# CAM_SENSOR.net
KiCad netlist of a schematic drawn in Altium Designer
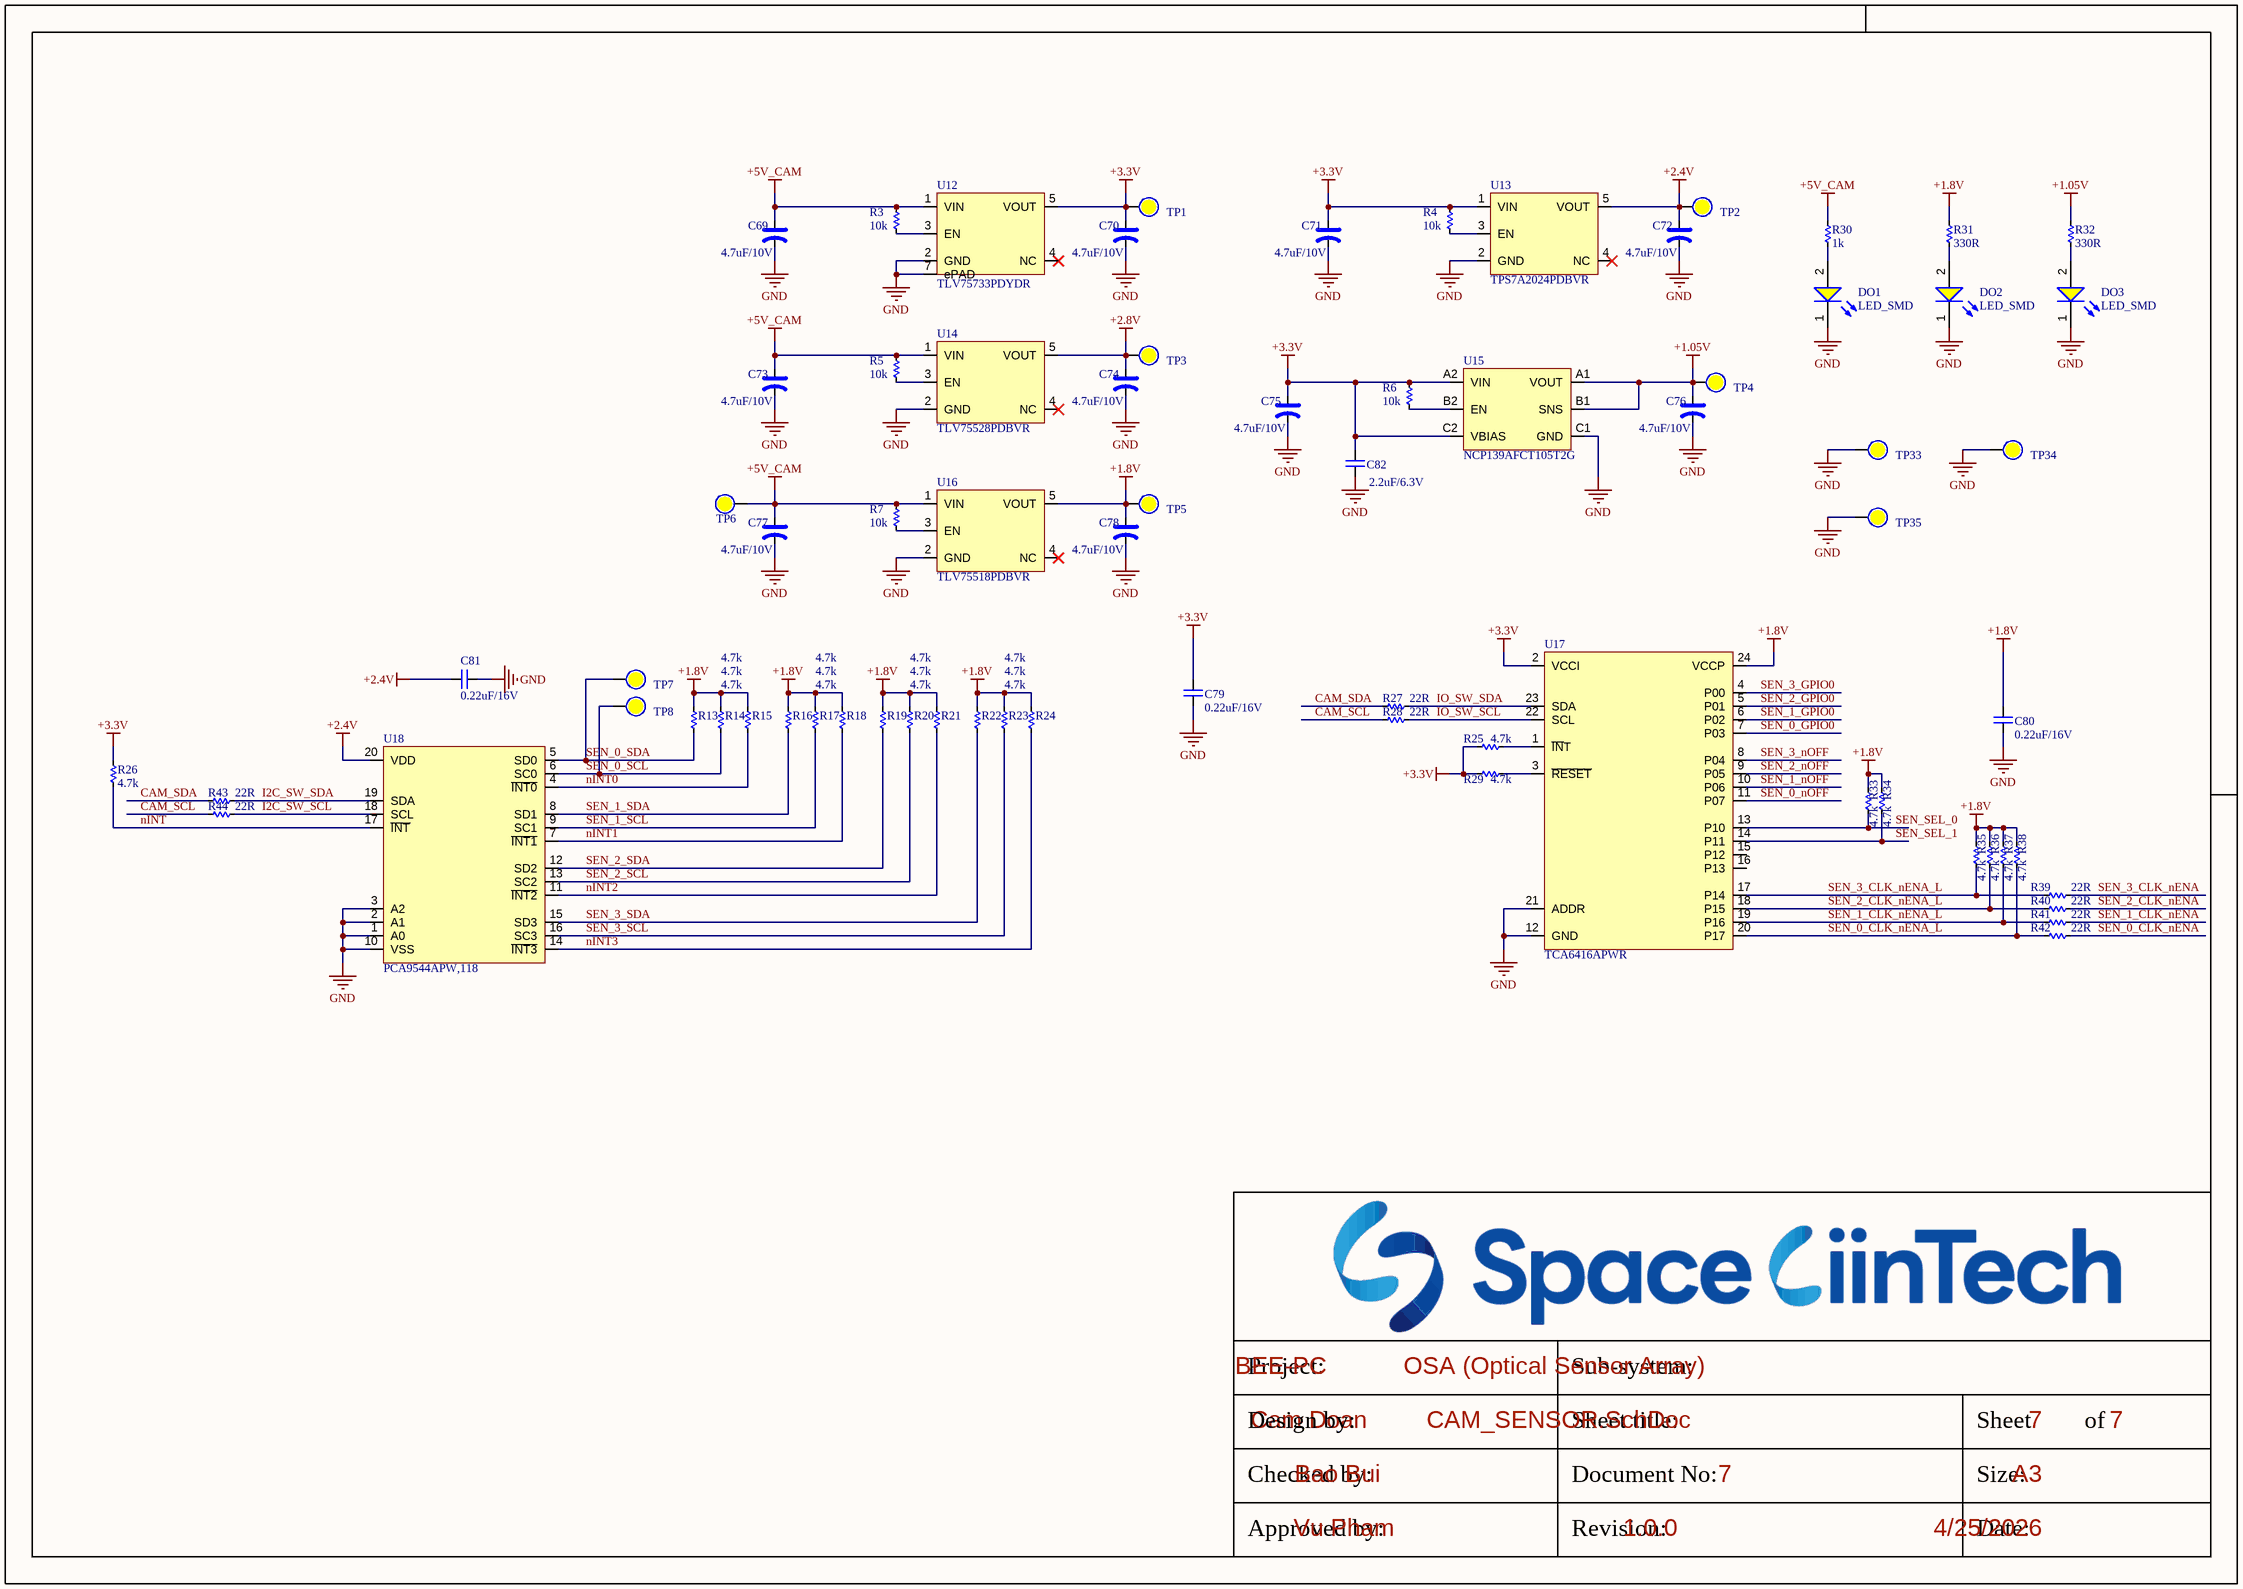
[diagram p0: CAM_SENSOR.SchDoc]

(export (version "E")
  (design (tool "Eeschema 10.0.6"))
  (components
    (comp (ref "C69")
      (value "4.7uF/10V")
      (footprint "CAP_MP_1608X90")
      (description "CAP_Polarization")
      (fields (field (name "PUBLISHER") "Altium Limited"))
      (libsource (lib "LABLIB") (part "CAP_TH"))
    )
    (comp (ref "C70")
      (value "4.7uF/10V")
      (footprint "CAP_MP_1608X90")
      (description "CAP_Polarization")
      (fields (field (name "PUBLISHER") "Altium Limited"))
      (libsource (lib "LABLIB") (part "CAP_TH"))
    )
    (comp (ref "C71")
      (value "4.7uF/10V")
      (footprint "CAP_MP_1608X90")
      (description "CAP_Polarization")
      (fields (field (name "PUBLISHER") "Altium Limited"))
      (libsource (lib "LABLIB") (part "CAP_TH"))
    )
    (comp (ref "C72")
      (value "4.7uF/10V")
      (footprint "CAP_MP_1608X90")
      (description "CAP_Polarization")
      (fields (field (name "PUBLISHER") "Altium Limited"))
      (libsource (lib "LABLIB") (part "CAP_TH"))
    )
    (comp (ref "C73")
      (value "4.7uF/10V")
      (footprint "CAP_MP_1608X90")
      (description "CAP_Polarization")
      (fields (field (name "PUBLISHER") "Altium Limited"))
      (libsource (lib "LABLIB") (part "CAP_TH"))
    )
    (comp (ref "C74")
      (value "4.7uF/10V")
      (footprint "CAP_MP_1608X90")
      (description "CAP_Polarization")
      (fields (field (name "PUBLISHER") "Altium Limited"))
      (libsource (lib "LABLIB") (part "CAP_TH"))
    )
    (comp (ref "C75")
      (value "4.7uF/10V")
      (footprint "CAP_MP_1608X90")
      (description "CAP_Polarization")
      (fields (field (name "PUBLISHER") "Altium Limited"))
      (libsource (lib "LABLIB") (part "CAP_TH"))
    )
    (comp (ref "C76")
      (value "4.7uF/10V")
      (footprint "CAP_MP_1608X90")
      (description "CAP_Polarization")
      (fields (field (name "PUBLISHER") "Altium Limited"))
      (libsource (lib "LABLIB") (part "CAP_TH"))
    )
    (comp (ref "C77")
      (value "4.7uF/10V")
      (footprint "CAP_MP_1608X90")
      (description "CAP_Polarization")
      (fields (field (name "PUBLISHER") "Altium Limited"))
      (libsource (lib "LABLIB") (part "CAP_TH"))
    )
    (comp (ref "C78")
      (value "4.7uF/10V")
      (footprint "CAP_MP_1608X90")
      (description "CAP_Polarization")
      (fields (field (name "PUBLISHER") "Altium Limited"))
      (libsource (lib "LABLIB") (part "CAP_TH"))
    )
    (comp (ref "C79")
      (value "0.22uF/16V")
      (footprint "CAP_C_1005X60")
      (description "CAP_Chip")
      (libsource (lib "LABLIB") (part "CAP_SMD"))
    )
    (comp (ref "C80")
      (value "0.22uF/16V")
      (footprint "CAP_C_1005X60")
      (description "CAP_Chip")
      (libsource (lib "LABLIB") (part "CAP_SMD"))
    )
    (comp (ref "C81")
      (value "0.22uF/16V")
      (footprint "CAP_C_1005X60")
      (description "CAP_Chip")
      (libsource (lib "LABLIB") (part "CAP_SMD"))
    )
    (comp (ref "C82")
      (value "2.2uF/6.3V")
      (footprint "CAP_C_1005X60")
      (description "CAP_Chip")
      (libsource (lib "LABLIB") (part "CAP_SMD"))
    )
    (comp (ref "DO1") (value "LED_SMD") (footprint "LED_0603") (libsource (lib "LABLIB") (part "LED_SMD")))
    (comp (ref "DO2") (value "LED_SMD") (footprint "LED_0603") (libsource (lib "LABLIB") (part "LED_SMD")))
    (comp (ref "DO3") (value "LED_SMD") (footprint "LED_0603") (libsource (lib "LABLIB") (part "LED_SMD")))
    (comp (ref "R3")
      (value "10k")
      (footprint "RES_C_1005X40")
      (description "RES-Chip")
      (fields
        (field (name "MANUFACTURER") "Generic Components")
        (field (name "PUBLISHER") "Altium Hobart Technology Centre")
      )
      (libsource (lib "LABLIB") (part "RES-SMD"))
    )
    (comp (ref "R4")
      (value "10k")
      (footprint "RES_C_1005X40")
      (description "RES-Chip")
      (fields
        (field (name "MANUFACTURER") "Generic Components")
        (field (name "PUBLISHER") "Altium Hobart Technology Centre")
      )
      (libsource (lib "LABLIB") (part "RES-SMD"))
    )
    (comp (ref "R5")
      (value "10k")
      (footprint "RES_C_1005X40")
      (description "RES-Chip")
      (fields
        (field (name "MANUFACTURER") "Generic Components")
        (field (name "PUBLISHER") "Altium Hobart Technology Centre")
      )
      (libsource (lib "LABLIB") (part "RES-SMD"))
    )
    (comp (ref "R6")
      (value "10k")
      (footprint "RES_C_1005X40")
      (description "RES-Chip")
      (fields
        (field (name "MANUFACTURER") "Generic Components")
        (field (name "PUBLISHER") "Altium Hobart Technology Centre")
      )
      (libsource (lib "LABLIB") (part "RES-SMD"))
    )
    (comp (ref "R7")
      (value "10k")
      (footprint "RES_C_1005X40")
      (description "RES-Chip")
      (fields
        (field (name "MANUFACTURER") "Generic Components")
        (field (name "PUBLISHER") "Altium Hobart Technology Centre")
      )
      (libsource (lib "LABLIB") (part "RES-SMD"))
    )
    (comp (ref "R13")
      (value "4.7k")
      (footprint "RES_C_1005X40")
      (description "RES-Chip")
      (fields
        (field (name "MANUFACTURER") "Generic Components")
        (field (name "PUBLISHER") "Altium Hobart Technology Centre")
      )
      (libsource (lib "LABLIB") (part "RES-SMD"))
    )
    (comp (ref "R14")
      (value "4.7k")
      (footprint "RES_C_1005X40")
      (description "RES-Chip")
      (fields
        (field (name "MANUFACTURER") "Generic Components")
        (field (name "PUBLISHER") "Altium Hobart Technology Centre")
      )
      (libsource (lib "LABLIB") (part "RES-SMD"))
    )
    (comp (ref "R15")
      (value "4.7k")
      (footprint "RES_C_1005X40")
      (description "RES-Chip")
      (fields
        (field (name "MANUFACTURER") "Generic Components")
        (field (name "PUBLISHER") "Altium Hobart Technology Centre")
      )
      (libsource (lib "LABLIB") (part "RES-SMD"))
    )
    (comp (ref "R16")
      (value "4.7k")
      (footprint "RES_C_1005X40")
      (description "RES-Chip")
      (fields
        (field (name "MANUFACTURER") "Generic Components")
        (field (name "PUBLISHER") "Altium Hobart Technology Centre")
      )
      (libsource (lib "LABLIB") (part "RES-SMD"))
    )
    (comp (ref "R17")
      (value "4.7k")
      (footprint "RES_C_1005X40")
      (description "RES-Chip")
      (fields
        (field (name "MANUFACTURER") "Generic Components")
        (field (name "PUBLISHER") "Altium Hobart Technology Centre")
      )
      (libsource (lib "LABLIB") (part "RES-SMD"))
    )
    (comp (ref "R18")
      (value "4.7k")
      (footprint "RES_C_1005X40")
      (description "RES-Chip")
      (fields
        (field (name "MANUFACTURER") "Generic Components")
        (field (name "PUBLISHER") "Altium Hobart Technology Centre")
      )
      (libsource (lib "LABLIB") (part "RES-SMD"))
    )
    (comp (ref "R19")
      (value "4.7k")
      (footprint "RES_C_1005X40")
      (description "RES-Chip")
      (fields
        (field (name "MANUFACTURER") "Generic Components")
        (field (name "PUBLISHER") "Altium Hobart Technology Centre")
      )
      (libsource (lib "LABLIB") (part "RES-SMD"))
    )
    (comp (ref "R20")
      (value "4.7k")
      (footprint "RES_C_1005X40")
      (description "RES-Chip")
      (fields
        (field (name "MANUFACTURER") "Generic Components")
        (field (name "PUBLISHER") "Altium Hobart Technology Centre")
      )
      (libsource (lib "LABLIB") (part "RES-SMD"))
    )
    (comp (ref "R21")
      (value "4.7k")
      (footprint "RES_C_1005X40")
      (description "RES-Chip")
      (fields
        (field (name "MANUFACTURER") "Generic Components")
        (field (name "PUBLISHER") "Altium Hobart Technology Centre")
      )
      (libsource (lib "LABLIB") (part "RES-SMD"))
    )
    (comp (ref "R22")
      (value "4.7k")
      (footprint "RES_C_1005X40")
      (description "RES-Chip")
      (fields
        (field (name "MANUFACTURER") "Generic Components")
        (field (name "PUBLISHER") "Altium Hobart Technology Centre")
      )
      (libsource (lib "LABLIB") (part "RES-SMD"))
    )
    (comp (ref "R23")
      (value "4.7k")
      (footprint "RES_C_1005X40")
      (description "RES-Chip")
      (fields
        (field (name "MANUFACTURER") "Generic Components")
        (field (name "PUBLISHER") "Altium Hobart Technology Centre")
      )
      (libsource (lib "LABLIB") (part "RES-SMD"))
    )
    (comp (ref "R24")
      (value "4.7k")
      (footprint "RES_C_1005X40")
      (description "RES-Chip")
      (fields
        (field (name "MANUFACTURER") "Generic Components")
        (field (name "PUBLISHER") "Altium Hobart Technology Centre")
      )
      (libsource (lib "LABLIB") (part "RES-SMD"))
    )
    (comp (ref "R25")
      (value "4.7k")
      (footprint "RES_C_1005X40")
      (description "RES-Chip")
      (fields
        (field (name "MANUFACTURER") "Generic Components")
        (field (name "PUBLISHER") "Altium Hobart Technology Centre")
      )
      (libsource (lib "LABLIB") (part "RES-SMD"))
    )
    (comp (ref "R26")
      (value "4.7k")
      (footprint "RES_C_1005X40")
      (description "RES-Chip")
      (fields
        (field (name "MANUFACTURER") "Generic Components")
        (field (name "PUBLISHER") "Altium Hobart Technology Centre")
      )
      (libsource (lib "LABLIB") (part "RES-SMD"))
    )
    (comp (ref "R27")
      (value "22R")
      (footprint "RES_C_1005X40")
      (description "RES-Chip")
      (fields
        (field (name "MANUFACTURER") "Generic Components")
        (field (name "PUBLISHER") "Altium Hobart Technology Centre")
      )
      (libsource (lib "LABLIB") (part "RES-SMD"))
    )
    (comp (ref "R28")
      (value "22R")
      (footprint "RES_C_1005X40")
      (description "RES-Chip")
      (fields
        (field (name "MANUFACTURER") "Generic Components")
        (field (name "PUBLISHER") "Altium Hobart Technology Centre")
      )
      (libsource (lib "LABLIB") (part "RES-SMD"))
    )
    (comp (ref "R29")
      (value "4.7k")
      (footprint "RES_C_1005X40")
      (description "RES-Chip")
      (fields
        (field (name "MANUFACTURER") "Generic Components")
        (field (name "PUBLISHER") "Altium Hobart Technology Centre")
      )
      (libsource (lib "LABLIB") (part "RES-SMD"))
    )
    (comp (ref "R30")
      (value "1k")
      (footprint "RES_C_1005X40")
      (description "RES-Chip")
      (fields
        (field (name "MANUFACTURER") "Generic Components")
        (field (name "PUBLISHER") "Altium Hobart Technology Centre")
      )
      (libsource (lib "LABLIB") (part "RES-SMD"))
    )
    (comp (ref "R31")
      (value "330R")
      (footprint "RES_C_1005X40")
      (description "RES-Chip")
      (fields
        (field (name "MANUFACTURER") "Generic Components")
        (field (name "PUBLISHER") "Altium Hobart Technology Centre")
      )
      (libsource (lib "LABLIB") (part "RES-SMD"))
    )
    (comp (ref "R32")
      (value "330R")
      (footprint "RES_C_1005X40")
      (description "RES-Chip")
      (fields
        (field (name "MANUFACTURER") "Generic Components")
        (field (name "PUBLISHER") "Altium Hobart Technology Centre")
      )
      (libsource (lib "LABLIB") (part "RES-SMD"))
    )
    (comp (ref "R33")
      (value "4.7k")
      (footprint "RES_C_1005X40")
      (description "RES-Chip")
      (fields
        (field (name "MANUFACTURER") "Generic Components")
        (field (name "PUBLISHER") "Altium Hobart Technology Centre")
      )
      (libsource (lib "LABLIB") (part "RES-SMD"))
    )
    (comp (ref "R34")
      (value "4.7k")
      (footprint "RES_C_1005X40")
      (description "RES-Chip")
      (fields
        (field (name "MANUFACTURER") "Generic Components")
        (field (name "PUBLISHER") "Altium Hobart Technology Centre")
      )
      (libsource (lib "LABLIB") (part "RES-SMD"))
    )
    (comp (ref "R35")
      (value "4.7k")
      (footprint "RES_C_1005X40")
      (description "RES-Chip")
      (fields
        (field (name "MANUFACTURER") "Generic Components")
        (field (name "PUBLISHER") "Altium Hobart Technology Centre")
      )
      (libsource (lib "LABLIB") (part "RES-SMD"))
    )
    (comp (ref "R36")
      (value "4.7k")
      (footprint "RES_C_1005X40")
      (description "RES-Chip")
      (fields
        (field (name "MANUFACTURER") "Generic Components")
        (field (name "PUBLISHER") "Altium Hobart Technology Centre")
      )
      (libsource (lib "LABLIB") (part "RES-SMD"))
    )
    (comp (ref "R37")
      (value "4.7k")
      (footprint "RES_C_1005X40")
      (description "RES-Chip")
      (fields
        (field (name "MANUFACTURER") "Generic Components")
        (field (name "PUBLISHER") "Altium Hobart Technology Centre")
      )
      (libsource (lib "LABLIB") (part "RES-SMD"))
    )
    (comp (ref "R38")
      (value "4.7k")
      (footprint "RES_C_1005X40")
      (description "RES-Chip")
      (fields
        (field (name "MANUFACTURER") "Generic Components")
        (field (name "PUBLISHER") "Altium Hobart Technology Centre")
      )
      (libsource (lib "LABLIB") (part "RES-SMD"))
    )
    (comp (ref "R39")
      (value "22R")
      (footprint "RES_C_1005X40")
      (description "RES-Chip")
      (fields
        (field (name "MANUFACTURER") "Generic Components")
        (field (name "PUBLISHER") "Altium Hobart Technology Centre")
      )
      (libsource (lib "LABLIB") (part "RES-SMD"))
    )
    (comp (ref "R40")
      (value "22R")
      (footprint "RES_C_1005X40")
      (description "RES-Chip")
      (fields
        (field (name "MANUFACTURER") "Generic Components")
        (field (name "PUBLISHER") "Altium Hobart Technology Centre")
      )
      (libsource (lib "LABLIB") (part "RES-SMD"))
    )
    (comp (ref "R41")
      (value "22R")
      (footprint "RES_C_1005X40")
      (description "RES-Chip")
      (fields
        (field (name "MANUFACTURER") "Generic Components")
        (field (name "PUBLISHER") "Altium Hobart Technology Centre")
      )
      (libsource (lib "LABLIB") (part "RES-SMD"))
    )
    (comp (ref "R42")
      (value "22R")
      (footprint "RES_C_1005X40")
      (description "RES-Chip")
      (fields
        (field (name "MANUFACTURER") "Generic Components")
        (field (name "PUBLISHER") "Altium Hobart Technology Centre")
      )
      (libsource (lib "LABLIB") (part "RES-SMD"))
    )
    (comp (ref "R43")
      (value "22R")
      (footprint "RES_C_1005X40")
      (description "RES-Chip")
      (fields
        (field (name "MANUFACTURER") "Generic Components")
        (field (name "PUBLISHER") "Altium Hobart Technology Centre")
      )
      (libsource (lib "LABLIB") (part "RES-SMD"))
    )
    (comp (ref "R44")
      (value "22R")
      (footprint "RES_C_1005X40")
      (description "RES-Chip")
      (fields
        (field (name "MANUFACTURER") "Generic Components")
        (field (name "PUBLISHER") "Altium Hobart Technology Centre")
      )
      (libsource (lib "LABLIB") (part "RES-SMD"))
    )
    (comp (ref "TP1")
      (value "~")
      (footprint "Testpoint_80_pin0")
      (description "Test Point")
      (libsource (lib "LABLIB") (part "Test Point"))
    )
    (comp (ref "TP2")
      (value "~")
      (footprint "Testpoint_80_pin0")
      (description "Test Point")
      (libsource (lib "LABLIB") (part "Test Point"))
    )
    (comp (ref "TP3")
      (value "~")
      (footprint "Testpoint_80_pin0")
      (description "Test Point")
      (libsource (lib "LABLIB") (part "Test Point"))
    )
    (comp (ref "TP4")
      (value "~")
      (footprint "Testpoint_80_pin0")
      (description "Test Point")
      (libsource (lib "LABLIB") (part "Test Point"))
    )
    (comp (ref "TP5")
      (value "~")
      (footprint "Testpoint_80_pin0")
      (description "Test Point")
      (libsource (lib "LABLIB") (part "Test Point"))
    )
    (comp (ref "TP6")
      (value "~")
      (footprint "Testpoint_80_pin0")
      (description "Test Point")
      (libsource (lib "") (part "Test Point_1"))
    )
    (comp (ref "TP7")
      (value "~")
      (footprint "Testpoint_80_pin0")
      (description "Test Point")
      (libsource (lib "LABLIB") (part "Test Point"))
    )
    (comp (ref "TP8")
      (value "~")
      (footprint "Testpoint_80_pin0")
      (description "Test Point")
      (libsource (lib "LABLIB") (part "Test Point"))
    )
    (comp (ref "TP33")
      (value "~")
      (footprint "Testpoint_80_pin0")
      (description "Test Point")
      (libsource (lib "LABLIB") (part "Test Point"))
    )
    (comp (ref "TP34")
      (value "~")
      (footprint "Testpoint_80_pin0")
      (description "Test Point")
      (libsource (lib "LABLIB") (part "Test Point"))
    )
    (comp (ref "TP35")
      (value "~")
      (footprint "Testpoint_80_pin0")
      (description "Test Point")
      (libsource (lib "LABLIB") (part "Test Point"))
    )
    (comp (ref "U12")
      (value "TLV75733PDYDR")
      (footprint "SOT25-EPAD")
      (libsource (lib "CAMERA_SchLib") (part "IC_POWER_TLV75733PDYDR"))
    )
    (comp (ref "U13")
      (value "TPS7A2024PDBVR")
      (footprint "SOT25")
      (libsource (lib "CAMERA_SchLib") (part "IC_POWER_AP7347DQ"))
    )
    (comp (ref "U14")
      (value "TLV75528PDBVR")
      (footprint "SOT25")
      (libsource (lib "CAMERA_SchLib") (part "IC_POWER_AP7347DQ"))
    )
    (comp (ref "U15")
      (value "NCP139AFCT105T2G")
      (footprint "WLCSP6")
      (libsource (lib "CAMERA_SchLib") (part "IC_POWER_NCP139AFCT105T2G"))
    )
    (comp (ref "U16")
      (value "TLV75518PDBVR")
      (footprint "SOT25")
      (libsource (lib "CAMERA_SchLib") (part "IC_POWER_AP7347DQ"))
    )
    (comp (ref "U17")
      (value "TCA6416APWR")
      (footprint "SOP65P440W-24N")
      (libsource (lib "CAMERA_SchLib") (part "IC_I2Cto16IO_TCA6416APWR"))
    )
    (comp (ref "U18")
      (value "PCA9544APW,118")
      (footprint "SOP65P440W_20")
      (libsource (lib "CAMERA_SchLib") (part "IC_I2CSW1to4_PCA9544APW,118"))
    )
  )
  (nets
    (net (code "1") (name "+1.05V") (class "Default")
      (node (ref "C76") (pin "1") (pinfunction "1_1") (pintype "passive"))
      (node (ref "R32") (pin "1") (pinfunction "1_1") (pintype "passive"))
      (node (ref "TP4") (pin "0") (pinfunction "0_0") (pintype "passive"))
      (node (ref "U15") (pin "A1") (pinfunction "VOUT_A1") (pintype "passive"))
      (node (ref "U15") (pin "B1") (pinfunction "SNS_B1") (pintype "passive"))
    )
    (net (code "2") (name "+1.8V") (class "Default")
      (node (ref "C78") (pin "1") (pinfunction "1_1") (pintype "passive"))
      (node (ref "C80") (pin "2") (pinfunction "2_2") (pintype "passive"))
      (node (ref "R13") (pin "1") (pinfunction "1_1") (pintype "passive"))
      (node (ref "R14") (pin "1") (pinfunction "1_1") (pintype "passive"))
      (node (ref "R15") (pin "1") (pinfunction "1_1") (pintype "passive"))
      (node (ref "R16") (pin "1") (pinfunction "1_1") (pintype "passive"))
      (node (ref "R17") (pin "1") (pinfunction "1_1") (pintype "passive"))
      (node (ref "R18") (pin "1") (pinfunction "1_1") (pintype "passive"))
      (node (ref "R19") (pin "1") (pinfunction "1_1") (pintype "passive"))
      (node (ref "R20") (pin "1") (pinfunction "1_1") (pintype "passive"))
      (node (ref "R21") (pin "1") (pinfunction "1_1") (pintype "passive"))
      (node (ref "R22") (pin "1") (pinfunction "1_1") (pintype "passive"))
      (node (ref "R23") (pin "1") (pinfunction "1_1") (pintype "passive"))
      (node (ref "R24") (pin "1") (pinfunction "1_1") (pintype "passive"))
      (node (ref "R31") (pin "1") (pinfunction "1_1") (pintype "passive"))
      (node (ref "R33") (pin "1") (pinfunction "1_1") (pintype "passive"))
      (node (ref "R34") (pin "1") (pinfunction "1_1") (pintype "passive"))
      (node (ref "R35") (pin "1") (pinfunction "1_1") (pintype "passive"))
      (node (ref "R36") (pin "1") (pinfunction "1_1") (pintype "passive"))
      (node (ref "R37") (pin "1") (pinfunction "1_1") (pintype "passive"))
      (node (ref "R38") (pin "1") (pinfunction "1_1") (pintype "passive"))
      (node (ref "TP5") (pin "0") (pinfunction "0_0") (pintype "passive"))
      (node (ref "U16") (pin "5") (pinfunction "VOUT_5") (pintype "passive"))
      (node (ref "U17") (pin "24") (pinfunction "VCCP_24") (pintype "passive"))
    )
    (net (code "3") (name "+2.4V") (class "Default")
      (node (ref "C72") (pin "1") (pinfunction "1_1") (pintype "passive"))
      (node (ref "C81") (pin "2") (pinfunction "2_2") (pintype "passive"))
      (node (ref "TP2") (pin "0") (pinfunction "0_0") (pintype "passive"))
      (node (ref "U13") (pin "5") (pinfunction "VOUT_5") (pintype "passive"))
      (node (ref "U18") (pin "20") (pinfunction "VDD_20") (pintype "passive"))
    )
    (net (code "4") (name "+2.8V") (class "Default")
      (node (ref "C74") (pin "1") (pinfunction "1_1") (pintype "passive"))
      (node (ref "TP3") (pin "0") (pinfunction "0_0") (pintype "passive"))
      (node (ref "U14") (pin "5") (pinfunction "VOUT_5") (pintype "passive"))
    )
    (net (code "5") (name "+3.3V") (class "Default")
      (node (ref "C70") (pin "1") (pinfunction "1_1") (pintype "passive"))
      (node (ref "C71") (pin "1") (pinfunction "1_1") (pintype "passive"))
      (node (ref "C75") (pin "1") (pinfunction "1_1") (pintype "passive"))
      (node (ref "C79") (pin "2") (pinfunction "2_2") (pintype "passive"))
      (node (ref "C82") (pin "2") (pinfunction "2_2") (pintype "passive"))
      (node (ref "R25") (pin "1") (pinfunction "1_1") (pintype "passive"))
      (node (ref "R26") (pin "1") (pinfunction "1_1") (pintype "passive"))
      (node (ref "R29") (pin "1") (pinfunction "1_1") (pintype "passive"))
      (node (ref "R4") (pin "2") (pinfunction "2_2") (pintype "passive"))
      (node (ref "R6") (pin "2") (pinfunction "2_2") (pintype "passive"))
      (node (ref "TP1") (pin "0") (pinfunction "0_0") (pintype "passive"))
      (node (ref "U12") (pin "5") (pinfunction "VOUT_5") (pintype "passive"))
      (node (ref "U13") (pin "1") (pinfunction "VIN_1") (pintype "passive"))
      (node (ref "U15") (pin "A2") (pinfunction "VIN_A2") (pintype "passive"))
      (node (ref "U15") (pin "C2") (pinfunction "VBIAS_C2") (pintype "passive"))
      (node (ref "U17") (pin "2") (pinfunction "VCCI_2") (pintype "passive"))
    )
    (net (code "6") (name "+5V_CAM") (class "Default")
      (node (ref "C69") (pin "1") (pinfunction "1_1") (pintype "passive"))
      (node (ref "C73") (pin "1") (pinfunction "1_1") (pintype "passive"))
      (node (ref "C77") (pin "1") (pinfunction "1_1") (pintype "passive"))
      (node (ref "R3") (pin "2") (pinfunction "2_2") (pintype "passive"))
      (node (ref "R30") (pin "1") (pinfunction "1_1") (pintype "passive"))
      (node (ref "R5") (pin "2") (pinfunction "2_2") (pintype "passive"))
      (node (ref "R7") (pin "2") (pinfunction "2_2") (pintype "passive"))
      (node (ref "TP6") (pin "0") (pinfunction "0_0") (pintype "passive"))
      (node (ref "U12") (pin "1") (pinfunction "VIN_1") (pintype "passive"))
      (node (ref "U14") (pin "1") (pinfunction "VIN_1") (pintype "passive"))
      (node (ref "U16") (pin "1") (pinfunction "VIN_1") (pintype "passive"))
    )
    (net (code "7") (name "/CAM_SCL") (class "Default")
      (node (ref "R28") (pin "2") (pinfunction "2_2") (pintype "passive"))
      (node (ref "R44") (pin "2") (pinfunction "2_2") (pintype "passive"))
    )
    (net (code "8") (name "/CAM_SDA") (class "Default")
      (node (ref "R27") (pin "2") (pinfunction "2_2") (pintype "passive"))
      (node (ref "R43") (pin "2") (pinfunction "2_2") (pintype "passive"))
    )
    (net (code "9") (name "/I2C_SW_SCL") (class "Default")
      (node (ref "R44") (pin "1") (pinfunction "1_1") (pintype "passive"))
      (node (ref "U18") (pin "18") (pinfunction "SCL_18") (pintype "passive"))
    )
    (net (code "10") (name "/I2C_SW_SDA") (class "Default")
      (node (ref "R43") (pin "1") (pinfunction "1_1") (pintype "passive"))
      (node (ref "U18") (pin "19") (pinfunction "SDA_19") (pintype "passive"))
    )
    (net (code "11") (name "/IO_SW_SCL") (class "Default")
      (node (ref "R28") (pin "1") (pinfunction "1_1") (pintype "passive"))
      (node (ref "U17") (pin "22") (pinfunction "SCL_22") (pintype "passive"))
    )
    (net (code "12") (name "/IO_SW_SDA") (class "Default")
      (node (ref "R27") (pin "1") (pinfunction "1_1") (pintype "passive"))
      (node (ref "U17") (pin "23") (pinfunction "SDA_23") (pintype "passive"))
    )
    (net (code "13") (name "/SEN_0_CLK_nENA") (class "Default")
      (node (ref "R42") (pin "1") (pinfunction "1_1") (pintype "passive"))
    )
    (net (code "14") (name "/SEN_0_CLK_nENA_L") (class "Default")
      (node (ref "R38") (pin "2") (pinfunction "2_2") (pintype "passive"))
      (node (ref "R42") (pin "2") (pinfunction "2_2") (pintype "passive"))
      (node (ref "U17") (pin "20") (pinfunction "P17_20") (pintype "passive"))
    )
    (net (code "15") (name "/SEN_0_GPIO0") (class "Default")
      (node (ref "U17") (pin "7") (pinfunction "P03_7") (pintype "passive"))
    )
    (net (code "16") (name "/SEN_0_SCL") (class "Default")
      (node (ref "R14") (pin "2") (pinfunction "2_2") (pintype "passive"))
      (node (ref "TP8") (pin "0") (pinfunction "0_0") (pintype "passive"))
      (node (ref "U18") (pin "6") (pinfunction "SC0_6") (pintype "passive"))
    )
    (net (code "17") (name "/SEN_0_SDA") (class "Default")
      (node (ref "R13") (pin "2") (pinfunction "2_2") (pintype "passive"))
      (node (ref "TP7") (pin "0") (pinfunction "0_0") (pintype "passive"))
      (node (ref "U18") (pin "5") (pinfunction "SD0_5") (pintype "passive"))
    )
    (net (code "18") (name "/SEN_0_nOFF") (class "Default")
      (node (ref "U17") (pin "11") (pinfunction "P07_11") (pintype "passive"))
    )
    (net (code "19") (name "/SEN_1_CLK_nENA") (class "Default")
      (node (ref "R41") (pin "1") (pinfunction "1_1") (pintype "passive"))
    )
    (net (code "20") (name "/SEN_1_CLK_nENA_L") (class "Default")
      (node (ref "R37") (pin "2") (pinfunction "2_2") (pintype "passive"))
      (node (ref "R41") (pin "2") (pinfunction "2_2") (pintype "passive"))
      (node (ref "U17") (pin "19") (pinfunction "P16_19") (pintype "passive"))
    )
    (net (code "21") (name "/SEN_1_GPIO0") (class "Default")
      (node (ref "U17") (pin "6") (pinfunction "P02_6") (pintype "passive"))
    )
    (net (code "22") (name "/SEN_1_SCL") (class "Default")
      (node (ref "R17") (pin "2") (pinfunction "2_2") (pintype "passive"))
      (node (ref "U18") (pin "9") (pinfunction "SC1_9") (pintype "passive"))
    )
    (net (code "23") (name "/SEN_1_SDA") (class "Default")
      (node (ref "R16") (pin "2") (pinfunction "2_2") (pintype "passive"))
      (node (ref "U18") (pin "8") (pinfunction "SD1_8") (pintype "passive"))
    )
    (net (code "24") (name "/SEN_1_nOFF") (class "Default")
      (node (ref "U17") (pin "10") (pinfunction "P06_10") (pintype "passive"))
    )
    (net (code "25") (name "/SEN_2_CLK_nENA") (class "Default")
      (node (ref "R40") (pin "1") (pinfunction "1_1") (pintype "passive"))
    )
    (net (code "26") (name "/SEN_2_CLK_nENA_L") (class "Default")
      (node (ref "R36") (pin "2") (pinfunction "2_2") (pintype "passive"))
      (node (ref "R40") (pin "2") (pinfunction "2_2") (pintype "passive"))
      (node (ref "U17") (pin "18") (pinfunction "P15_18") (pintype "passive"))
    )
    (net (code "27") (name "/SEN_2_GPIO0") (class "Default")
      (node (ref "U17") (pin "5") (pinfunction "P01_5") (pintype "passive"))
    )
    (net (code "28") (name "/SEN_2_SCL") (class "Default")
      (node (ref "R20") (pin "2") (pinfunction "2_2") (pintype "passive"))
      (node (ref "U18") (pin "13") (pinfunction "SC2_13") (pintype "passive"))
    )
    (net (code "29") (name "/SEN_2_SDA") (class "Default")
      (node (ref "R19") (pin "2") (pinfunction "2_2") (pintype "passive"))
      (node (ref "U18") (pin "12") (pinfunction "SD2_12") (pintype "passive"))
    )
    (net (code "30") (name "/SEN_2_nOFF") (class "Default")
      (node (ref "U17") (pin "9") (pinfunction "P05_9") (pintype "passive"))
    )
    (net (code "31") (name "/SEN_3_CLK_nENA") (class "Default")
      (node (ref "R39") (pin "1") (pinfunction "1_1") (pintype "passive"))
    )
    (net (code "32") (name "/SEN_3_CLK_nENA_L") (class "Default")
      (node (ref "R35") (pin "2") (pinfunction "2_2") (pintype "passive"))
      (node (ref "R39") (pin "2") (pinfunction "2_2") (pintype "passive"))
      (node (ref "U17") (pin "17") (pinfunction "P14_17") (pintype "passive"))
    )
    (net (code "33") (name "/SEN_3_GPIO0") (class "Default")
      (node (ref "U17") (pin "4") (pinfunction "P00_4") (pintype "passive"))
    )
    (net (code "34") (name "/SEN_3_SCL") (class "Default")
      (node (ref "R23") (pin "2") (pinfunction "2_2") (pintype "passive"))
      (node (ref "U18") (pin "16") (pinfunction "SC3_16") (pintype "passive"))
    )
    (net (code "35") (name "/SEN_3_SDA") (class "Default")
      (node (ref "R22") (pin "2") (pinfunction "2_2") (pintype "passive"))
      (node (ref "U18") (pin "15") (pinfunction "SD3_15") (pintype "passive"))
    )
    (net (code "36") (name "/SEN_3_nOFF") (class "Default")
      (node (ref "U17") (pin "8") (pinfunction "P04_8") (pintype "passive"))
    )
    (net (code "37") (name "/SEN_SEL_0") (class "Default")
      (node (ref "R33") (pin "2") (pinfunction "2_2") (pintype "passive"))
      (node (ref "U17") (pin "13") (pinfunction "P10_13") (pintype "passive"))
    )
    (net (code "38") (name "/SEN_SEL_1") (class "Default")
      (node (ref "R34") (pin "2") (pinfunction "2_2") (pintype "passive"))
      (node (ref "U17") (pin "14") (pinfunction "P11_14") (pintype "passive"))
    )
    (net (code "39") (name "/nINT") (class "Default")
      (node (ref "R26") (pin "2") (pinfunction "2_2") (pintype "passive"))
      (node (ref "U18") (pin "17") (pinfunction "~{INT}_17") (pintype "passive"))
    )
    (net (code "40") (name "/nINT0") (class "Default")
      (node (ref "R15") (pin "2") (pinfunction "2_2") (pintype "passive"))
      (node (ref "U18") (pin "4") (pinfunction "~{INT0}_4") (pintype "passive"))
    )
    (net (code "41") (name "/nINT1") (class "Default")
      (node (ref "R18") (pin "2") (pinfunction "2_2") (pintype "passive"))
      (node (ref "U18") (pin "7") (pinfunction "~{INT1}_7") (pintype "passive"))
    )
    (net (code "42") (name "/nINT2") (class "Default")
      (node (ref "R21") (pin "2") (pinfunction "2_2") (pintype "passive"))
      (node (ref "U18") (pin "11") (pinfunction "~{INT2}_11") (pintype "passive"))
    )
    (net (code "43") (name "/nINT3") (class "Default")
      (node (ref "R24") (pin "2") (pinfunction "2_2") (pintype "passive"))
      (node (ref "U18") (pin "14") (pinfunction "~{INT3}_14") (pintype "passive"))
    )
    (net (code "44") (name "GND") (class "Default")
      (node (ref "C69") (pin "2") (pinfunction "2_2") (pintype "passive"))
      (node (ref "C70") (pin "2") (pinfunction "2_2") (pintype "passive"))
      (node (ref "C71") (pin "2") (pinfunction "2_2") (pintype "passive"))
      (node (ref "C72") (pin "2") (pinfunction "2_2") (pintype "passive"))
      (node (ref "C73") (pin "2") (pinfunction "2_2") (pintype "passive"))
      (node (ref "C74") (pin "2") (pinfunction "2_2") (pintype "passive"))
      (node (ref "C75") (pin "2") (pinfunction "2_2") (pintype "passive"))
      (node (ref "C76") (pin "2") (pinfunction "2_2") (pintype "passive"))
      (node (ref "C77") (pin "2") (pinfunction "2_2") (pintype "passive"))
      (node (ref "C78") (pin "2") (pinfunction "2_2") (pintype "passive"))
      (node (ref "C79") (pin "1") (pinfunction "1_1") (pintype "passive"))
      (node (ref "C80") (pin "1") (pinfunction "1_1") (pintype "passive"))
      (node (ref "C81") (pin "1") (pinfunction "1_1") (pintype "passive"))
      (node (ref "C82") (pin "1") (pinfunction "1_1") (pintype "passive"))
      (node (ref "DO1") (pin "1") (pinfunction "K_1") (pintype "passive"))
      (node (ref "DO2") (pin "1") (pinfunction "K_1") (pintype "passive"))
      (node (ref "DO3") (pin "1") (pinfunction "K_1") (pintype "passive"))
      (node (ref "TP33") (pin "0") (pinfunction "0_0") (pintype "passive"))
      (node (ref "TP34") (pin "0") (pinfunction "0_0") (pintype "passive"))
      (node (ref "TP35") (pin "0") (pinfunction "0_0") (pintype "passive"))
      (node (ref "U12") (pin "2") (pinfunction "GND_2") (pintype "passive"))
      (node (ref "U12") (pin "7") (pinfunction "ePAD_7") (pintype "passive"))
      (node (ref "U13") (pin "2") (pinfunction "GND_2") (pintype "passive"))
      (node (ref "U14") (pin "2") (pinfunction "GND_2") (pintype "passive"))
      (node (ref "U15") (pin "C1") (pinfunction "GND_C1") (pintype "passive"))
      (node (ref "U16") (pin "2") (pinfunction "GND_2") (pintype "passive"))
      (node (ref "U17") (pin "12") (pinfunction "GND_12") (pintype "passive"))
      (node (ref "U17") (pin "21") (pinfunction "ADDR_21") (pintype "passive"))
      (node (ref "U18") (pin "1") (pinfunction "A0_1") (pintype "passive"))
      (node (ref "U18") (pin "10") (pinfunction "VSS_10") (pintype "passive"))
      (node (ref "U18") (pin "2") (pinfunction "A1_2") (pintype "passive"))
      (node (ref "U18") (pin "3") (pinfunction "A2_3") (pintype "passive"))
    )
    (net (code "45") (name "Net-(DO1-A)") (class "Default")
      (node (ref "DO1") (pin "2") (pinfunction "A_2") (pintype "passive"))
      (node (ref "R30") (pin "2") (pinfunction "2_2") (pintype "passive"))
    )
    (net (code "46") (name "Net-(DO2-A)") (class "Default")
      (node (ref "DO2") (pin "2") (pinfunction "A_2") (pintype "passive"))
      (node (ref "R31") (pin "2") (pinfunction "2_2") (pintype "passive"))
    )
    (net (code "47") (name "Net-(DO3-A)") (class "Default")
      (node (ref "DO3") (pin "2") (pinfunction "A_2") (pintype "passive"))
      (node (ref "R32") (pin "2") (pinfunction "2_2") (pintype "passive"))
    )
    (net (code "48") (name "Net-(U12-EN)") (class "Default")
      (node (ref "R3") (pin "1") (pinfunction "1_1") (pintype "passive"))
      (node (ref "U12") (pin "3") (pinfunction "EN_3") (pintype "passive"))
    )
    (net (code "49") (name "Net-(U13-EN)") (class "Default")
      (node (ref "R4") (pin "1") (pinfunction "1_1") (pintype "passive"))
      (node (ref "U13") (pin "3") (pinfunction "EN_3") (pintype "passive"))
    )
    (net (code "50") (name "Net-(U14-EN)") (class "Default")
      (node (ref "R5") (pin "1") (pinfunction "1_1") (pintype "passive"))
      (node (ref "U14") (pin "3") (pinfunction "EN_3") (pintype "passive"))
    )
    (net (code "51") (name "Net-(U15-EN)") (class "Default")
      (node (ref "R6") (pin "1") (pinfunction "1_1") (pintype "passive"))
      (node (ref "U15") (pin "B2") (pinfunction "EN_B2") (pintype "passive"))
    )
    (net (code "52") (name "Net-(U16-EN)") (class "Default")
      (node (ref "R7") (pin "1") (pinfunction "1_1") (pintype "passive"))
      (node (ref "U16") (pin "3") (pinfunction "EN_3") (pintype "passive"))
    )
    (net (code "53") (name "Net-(U17-~{IN}T)") (class "Default")
      (node (ref "R25") (pin "2") (pinfunction "2_2") (pintype "passive"))
      (node (ref "U17") (pin "1") (pinfunction "~{IN}T_1") (pintype "passive"))
    )
    (net (code "54") (name "Net-(U17-~{RESET})") (class "Default")
      (node (ref "R29") (pin "2") (pinfunction "2_2") (pintype "passive"))
      (node (ref "U17") (pin "3") (pinfunction "~{RESET}_3") (pintype "passive"))
    )
    (net (code "55") (name "unconnected-(U12-NC-Pad4)") (class "Default")
      (node (ref "U12") (pin "4") (pinfunction "NC_4") (pintype "passive+no_connect"))
    )
    (net (code "56") (name "unconnected-(U13-NC-Pad4)") (class "Default")
      (node (ref "U13") (pin "4") (pinfunction "NC_4") (pintype "passive+no_connect"))
    )
    (net (code "57") (name "unconnected-(U14-NC-Pad4)") (class "Default")
      (node (ref "U14") (pin "4") (pinfunction "NC_4") (pintype "passive+no_connect"))
    )
    (net (code "58") (name "unconnected-(U16-NC-Pad4)") (class "Default")
      (node (ref "U16") (pin "4") (pinfunction "NC_4") (pintype "passive+no_connect"))
    )
    (net (code "59") (name "unconnected-(U17-P12-Pad15)") (class "Default")
      (node (ref "U17") (pin "15") (pinfunction "P12_15") (pintype "passive"))
    )
    (net (code "60") (name "unconnected-(U17-P13-Pad16)") (class "Default")
      (node (ref "U17") (pin "16") (pinfunction "P13_16") (pintype "passive"))
    )
  )
)
